# motor-shield.net
KiCad netlist of a schematic drawn in EAGLE
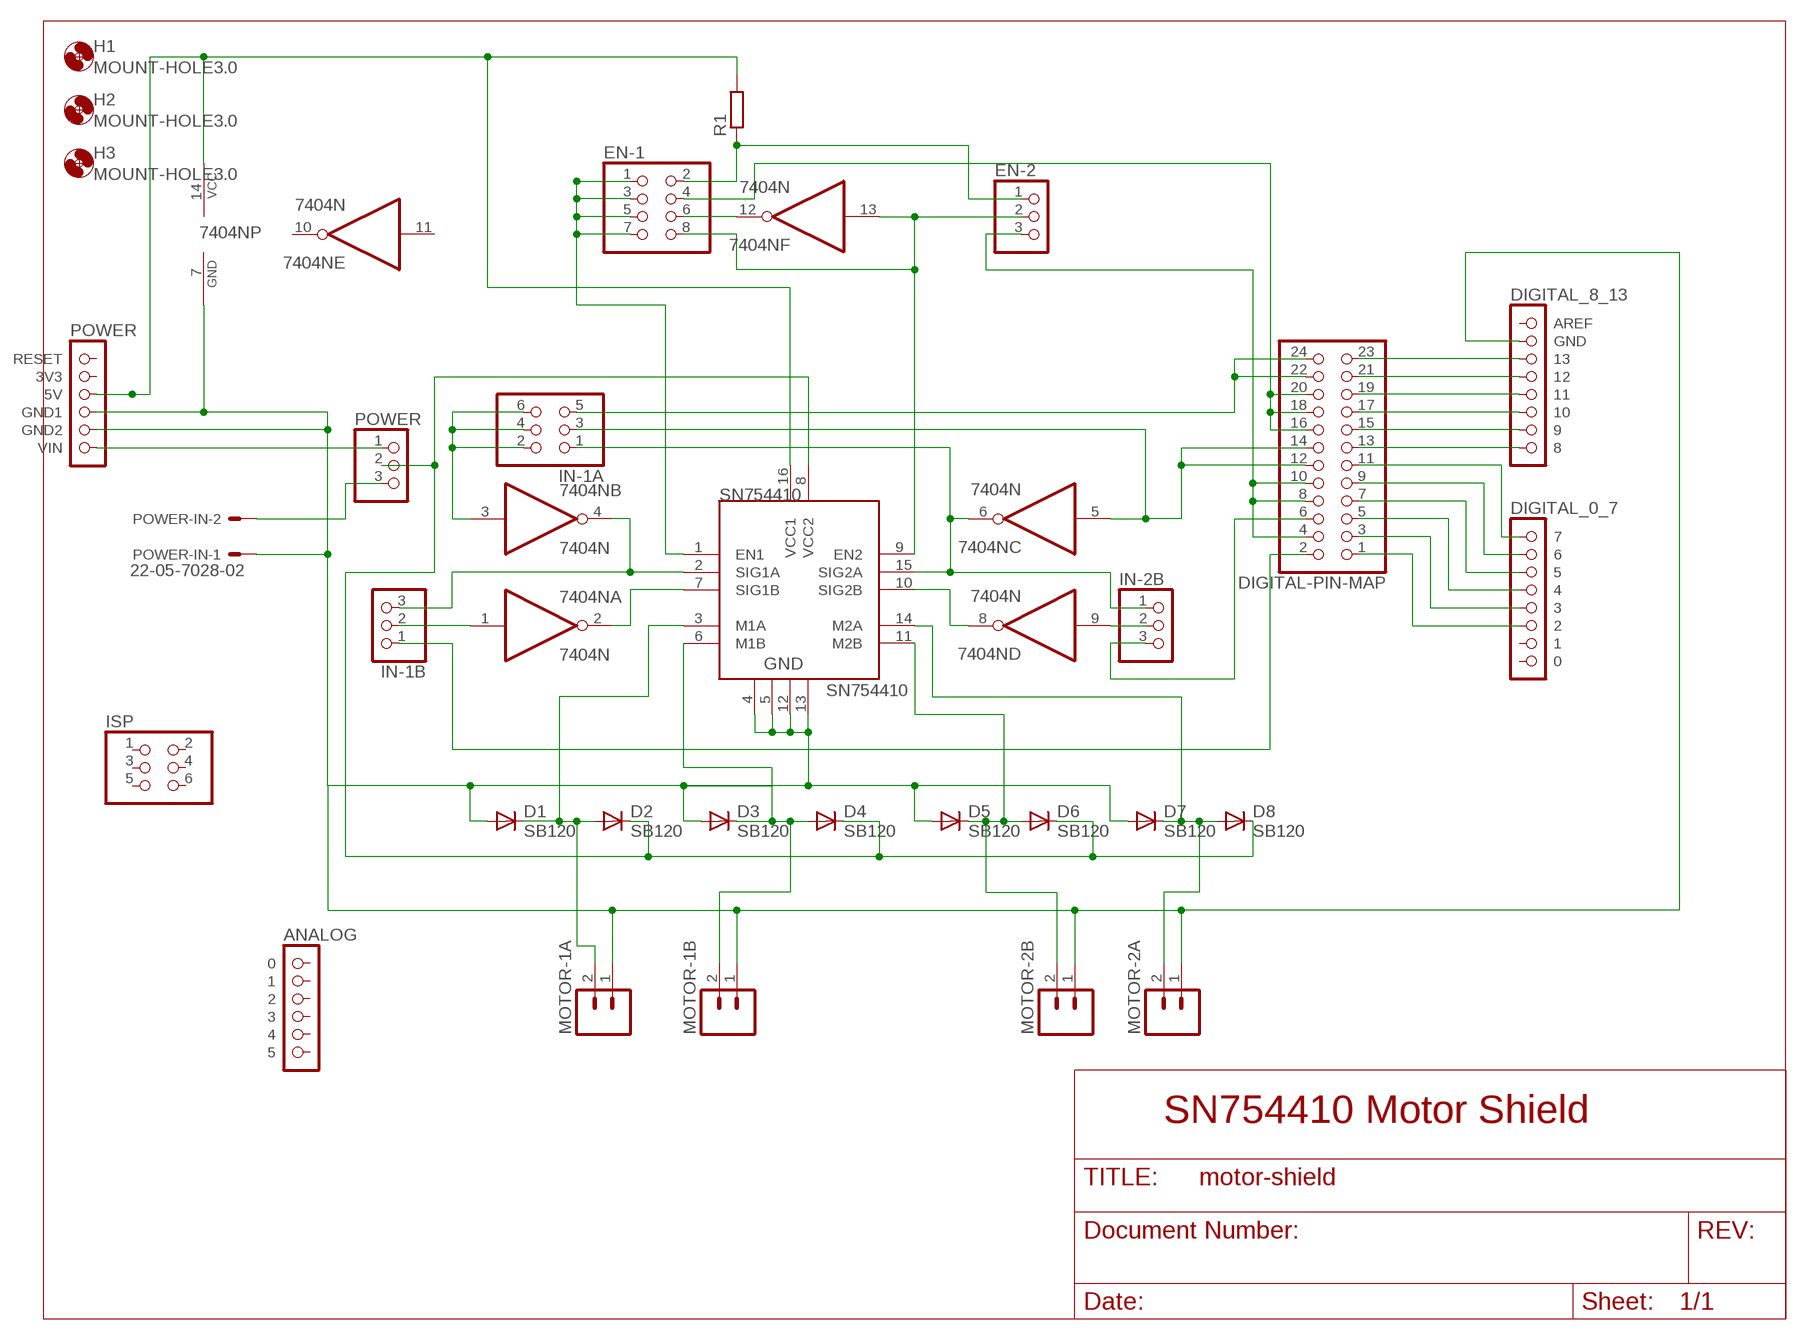
[diagram p0: schematic, sheet 1]

(export (version "E")
  (design (tool "Eeschema 10.0.6"))
  (components
    (comp (ref "7404N")
      (value "7404N")
      (footprint "eagle-import:DIL14")
      (libsource (lib "eagle-import") (part "7404N"))
    )
    (comp (ref "D1")
      (value "SB120")
      (footprint "eagle-import:DO41-10")
      (libsource (lib "eagle-import") (part "SB120"))
    )
    (comp (ref "D2")
      (value "SB120")
      (footprint "eagle-import:DO41-10")
      (libsource (lib "eagle-import") (part "SB120"))
    )
    (comp (ref "D3")
      (value "SB120")
      (footprint "eagle-import:DO41-10")
      (libsource (lib "eagle-import") (part "SB120"))
    )
    (comp (ref "D4")
      (value "SB120")
      (footprint "eagle-import:DO41-10")
      (libsource (lib "eagle-import") (part "SB120"))
    )
    (comp (ref "D5")
      (value "SB120")
      (footprint "eagle-import:DO41-10")
      (libsource (lib "eagle-import") (part "SB120"))
    )
    (comp (ref "D6")
      (value "SB120")
      (footprint "eagle-import:DO41-10")
      (libsource (lib "eagle-import") (part "SB120"))
    )
    (comp (ref "D7")
      (value "SB120")
      (footprint "eagle-import:DO41-10")
      (libsource (lib "eagle-import") (part "SB120"))
    )
    (comp (ref "D8")
      (value "SB120")
      (footprint "eagle-import:DO41-10")
      (libsource (lib "eagle-import") (part "SB120"))
    )
    (comp (ref "DIGITAL-PIN-MAP")
      (value "PINHD-2X12")
      (footprint "eagle-import:2X12")
      (libsource (lib "eagle-import") (part "PINHD-2X12"))
    )
    (comp (ref "EN-1")
      (value "PINHD-2X4")
      (footprint "eagle-import:2X04")
      (libsource (lib "eagle-import") (part "PINHD-2X4"))
    )
    (comp (ref "EN-2")
      (value "PINHD-1X3")
      (footprint "eagle-import:1X03")
      (libsource (lib "eagle-import") (part "PINHD-1X3"))
    )
    (comp (ref "H1")
      (value "MOUNT-HOLE3.0")
      (footprint "eagle-import:3,0")
      (libsource (lib "eagle-import") (part "MOUNT-HOLE3.0"))
    )
    (comp (ref "H2")
      (value "MOUNT-HOLE3.0")
      (footprint "eagle-import:3,0")
      (libsource (lib "eagle-import") (part "MOUNT-HOLE3.0"))
    )
    (comp (ref "H3")
      (value "MOUNT-HOLE3.0")
      (footprint "eagle-import:3,0")
      (libsource (lib "eagle-import") (part "MOUNT-HOLE3.0"))
    )
    (comp (ref "IN-1A")
      (value "PINHD-2X3")
      (footprint "eagle-import:2X03")
      (libsource (lib "eagle-import") (part "PINHD-2X3"))
    )
    (comp (ref "IN-1B")
      (value "PINHD-1X3")
      (footprint "eagle-import:1X03")
      (libsource (lib "eagle-import") (part "PINHD-1X3"))
    )
    (comp (ref "IN-2B")
      (value "PINHD-1X3")
      (footprint "eagle-import:1X03")
      (libsource (lib "eagle-import") (part "PINHD-1X3"))
    )
    (comp (ref "ISP")
      (value "PINHD-2X3")
      (footprint "eagle-import:2X03")
      (libsource (lib "eagle-import") (part "PINHD-2X3"))
    )
    (comp (ref "MOTOR-1A")
      (value "M023.5MM-NO_SILK")
      (footprint "eagle-import:SCREWTERMINAL-3.5MM-2-NS")
      (libsource (lib "eagle-import") (part "M023.5MM-NO_SILK"))
    )
    (comp (ref "MOTOR-1B")
      (value "M023.5MM-NO_SILK")
      (footprint "eagle-import:SCREWTERMINAL-3.5MM-2-NS")
      (libsource (lib "eagle-import") (part "M023.5MM-NO_SILK"))
    )
    (comp (ref "MOTOR-2A")
      (value "M023.5MM-NO_SILK")
      (footprint "eagle-import:SCREWTERMINAL-3.5MM-2-NS")
      (libsource (lib "eagle-import") (part "M023.5MM-NO_SILK"))
    )
    (comp (ref "MOTOR-2B")
      (value "M023.5MM-NO_SILK")
      (footprint "eagle-import:SCREWTERMINAL-3.5MM-2-NS")
      (libsource (lib "eagle-import") (part "M023.5MM-NO_SILK"))
    )
    (comp (ref "POWER")
      (value "PINHD-1X3")
      (footprint "eagle-import:1X03")
      (libsource (lib "eagle-import") (part "PINHD-1X3"))
    )
    (comp (ref "POWER-IN")
      (value "22-05-7028-02")
      (footprint "eagle-import:7395-02")
      (libsource (lib "eagle-import") (part "22-?-0205-7028"))
    )
    (comp (ref "R1")
      (value "R-EU_0207/10")
      (footprint "eagle-import:0207_10")
      (libsource (lib "eagle-import") (part "R-EU_0207/10"))
    )
    (comp (ref "SN754410")
      (value "SN754410")
      (footprint "eagle-import:DIP16")
      (libsource (lib "eagle-import") (part "SN754410"))
    )
    (comp (ref "U$1")
      (value "POWER")
      (footprint "eagle-import:1X06")
      (libsource (lib "eagle-import") (part "POWER"))
    )
    (comp (ref "U$2")
      (value "ANALOG")
      (footprint "eagle-import:1X06")
      (libsource (lib "eagle-import") (part "ANALOG"))
    )
    (comp (ref "U$3")
      (value "DIGITAL_0_7")
      (footprint "eagle-import:1X08")
      (libsource (lib "eagle-import") (part "DIGITAL_0_7"))
    )
    (comp (ref "U$4")
      (value "DIGITAL_8_13")
      (footprint "eagle-import:1X08")
      (libsource (lib "eagle-import") (part "DIGITAL_8_13"))
    )
  )
  (nets
    (net (code "1") (name "Net-(7404NA-I)") (class "Default")
      (node (ref "7404N") (pin "1") (pinfunction "I_1") (pintype "input"))
      (node (ref "IN-1B") (pin "2") (pinfunction "2_2") (pintype "passive"))
    )
    (net (code "2") (name "Net-(7404NA-O)") (class "Default")
      (node (ref "7404N") (pin "2") (pinfunction "O_2") (pintype "output"))
      (node (ref "SN754410") (pin "7") (pinfunction "SIG1B_7") (pintype "bidirectional"))
    )
    (net (code "3") (name "Net-(7404NB-I)") (class "Default")
      (node (ref "7404N") (pin "3") (pinfunction "I_3") (pintype "input"))
      (node (ref "IN-1A") (pin "2") (pinfunction "2_2") (pintype "passive"))
      (node (ref "IN-1A") (pin "4") (pinfunction "4_4") (pintype "passive"))
      (node (ref "IN-1A") (pin "6") (pinfunction "6_6") (pintype "passive"))
    )
    (net (code "4") (name "Net-(7404NB-O)") (class "Default")
      (node (ref "7404N") (pin "4") (pinfunction "O_4") (pintype "output"))
      (node (ref "IN-1B") (pin "3") (pinfunction "3_3") (pintype "passive"))
      (node (ref "SN754410") (pin "2") (pinfunction "SIG1A_2") (pintype "bidirectional"))
    )
    (net (code "5") (name "Net-(7404NC-I)") (class "Default")
      (node (ref "7404N") (pin "5") (pinfunction "I_5") (pintype "input"))
      (node (ref "DIGITAL-PIN-MAP") (pin "12") (pinfunction "12_12") (pintype "passive"))
      (node (ref "DIGITAL-PIN-MAP") (pin "14") (pinfunction "14_14") (pintype "passive"))
      (node (ref "IN-1A") (pin "3") (pinfunction "3_3") (pintype "passive"))
    )
    (net (code "6") (name "Net-(7404NC-O)") (class "Default")
      (node (ref "7404N") (pin "6") (pinfunction "O_6") (pintype "output"))
      (node (ref "IN-1A") (pin "1") (pinfunction "1_1") (pintype "passive"))
      (node (ref "IN-2B") (pin "1") (pinfunction "1_1") (pintype "passive"))
      (node (ref "SN754410") (pin "15") (pinfunction "SIG2A_15") (pintype "bidirectional"))
    )
    (net (code "7") (name "Net-(7404ND-I)") (class "Default")
      (node (ref "7404N") (pin "9") (pinfunction "I_9") (pintype "input"))
      (node (ref "IN-2B") (pin "2") (pinfunction "2_2") (pintype "passive"))
    )
    (net (code "8") (name "Net-(7404ND-O)") (class "Default")
      (node (ref "7404N") (pin "8") (pinfunction "O_8") (pintype "output"))
      (node (ref "SN754410") (pin "10") (pinfunction "SIG2B_10") (pintype "bidirectional"))
    )
    (net (code "9") (name "Net-(7404NF-I)") (class "Default")
      (node (ref "7404N") (pin "13") (pinfunction "I_13") (pintype "input"))
      (node (ref "EN-1") (pin "8") (pinfunction "8_8") (pintype "passive"))
      (node (ref "EN-2") (pin "2") (pinfunction "2_2") (pintype "passive"))
      (node (ref "SN754410") (pin "9") (pinfunction "EN2_9") (pintype "bidirectional"))
    )
    (net (code "10") (name "Net-(7404NF-O)") (class "Default")
      (node (ref "7404N") (pin "12") (pinfunction "O_12") (pintype "output"))
      (node (ref "EN-1") (pin "6") (pinfunction "6_6") (pintype "passive"))
    )
    (net (code "11") (name "Net-(7404NG-GND)") (class "Default")
      (node (ref "7404N") (pin "7") (pinfunction "GND_7") (pintype "power_in"))
      (node (ref "D1") (pin "A") (pinfunction "A_A") (pintype "passive"))
      (node (ref "D3") (pin "A") (pinfunction "A_A") (pintype "passive"))
      (node (ref "D5") (pin "A") (pinfunction "A_A") (pintype "passive"))
      (node (ref "D7") (pin "A") (pinfunction "A_A") (pintype "passive"))
      (node (ref "MOTOR-1A") (pin "1") (pinfunction "1_1") (pintype "passive"))
      (node (ref "MOTOR-1B") (pin "1") (pinfunction "1_1") (pintype "passive"))
      (node (ref "MOTOR-2A") (pin "1") (pinfunction "1_1") (pintype "passive"))
      (node (ref "MOTOR-2B") (pin "1") (pinfunction "1_1") (pintype "passive"))
      (node (ref "POWER-IN") (pin "1") (pinfunction "S_1") (pintype "passive"))
      (node (ref "SN754410") (pin "12") (pinfunction "P12_12") (pintype "power_in"))
      (node (ref "SN754410") (pin "13") (pinfunction "P13_13") (pintype "power_in"))
      (node (ref "SN754410") (pin "4") (pinfunction "P4_4") (pintype "power_in"))
      (node (ref "SN754410") (pin "5") (pinfunction "P5_5") (pintype "power_in"))
      (node (ref "U$1") (pin "4") (pinfunction "GND1_4") (pintype "passive"))
      (node (ref "U$1") (pin "5") (pinfunction "GND2_5") (pintype "passive"))
      (node (ref "U$4") (pin "2") (pinfunction "GND_2") (pintype "passive"))
    )
    (net (code "12") (name "Net-(7404NG-VCC)") (class "Default")
      (node (ref "7404N") (pin "14") (pinfunction "VCC_14") (pintype "power_in"))
      (node (ref "R1") (pin "2") (pinfunction "2_2") (pintype "passive"))
      (node (ref "SN754410") (pin "16") (pinfunction "VCC1_16") (pintype "power_in"))
      (node (ref "U$1") (pin "3") (pinfunction "5V_3") (pintype "passive"))
    )
    (net (code "13") (name "Net-(DIGITAL-PIN-MAP-Pad2)") (class "Default")
      (node (ref "DIGITAL-PIN-MAP") (pin "2") (pinfunction "2_2") (pintype "passive"))
      (node (ref "IN-1B") (pin "1") (pinfunction "1_1") (pintype "passive"))
    )
    (net (code "14") (name "Net-(DIGITAL-PIN-MAP-Pad5)") (class "Default")
      (node (ref "DIGITAL-PIN-MAP") (pin "5") (pinfunction "5_5") (pintype "passive"))
      (node (ref "U$3") (pin "4") (pinfunction "4_4") (pintype "passive"))
    )
    (net (code "15") (name "Net-(DIGITAL-PIN-MAP-Pad6)") (class "Default")
      (node (ref "DIGITAL-PIN-MAP") (pin "6") (pinfunction "6_6") (pintype "passive"))
      (node (ref "IN-2B") (pin "3") (pinfunction "3_3") (pintype "passive"))
    )
    (net (code "16") (name "Net-(DIGITAL-PIN-MAP-Pad10)") (class "Default")
      (node (ref "DIGITAL-PIN-MAP") (pin "10") (pinfunction "10_10") (pintype "passive"))
      (node (ref "DIGITAL-PIN-MAP") (pin "4") (pinfunction "4_4") (pintype "passive"))
      (node (ref "DIGITAL-PIN-MAP") (pin "8") (pinfunction "8_8") (pintype "passive"))
      (node (ref "EN-2") (pin "3") (pinfunction "3_3") (pintype "passive"))
    )
    (net (code "17") (name "Net-(DIGITAL-PIN-MAP-Pad13)") (class "Default")
      (node (ref "DIGITAL-PIN-MAP") (pin "13") (pinfunction "13_13") (pintype "passive"))
      (node (ref "U$4") (pin "8") (pinfunction "8_8") (pintype "passive"))
    )
    (net (code "18") (name "Net-(DIGITAL-PIN-MAP-Pad16)") (class "Default")
      (node (ref "DIGITAL-PIN-MAP") (pin "16") (pinfunction "16_16") (pintype "passive"))
      (node (ref "DIGITAL-PIN-MAP") (pin "18") (pinfunction "18_18") (pintype "passive"))
      (node (ref "DIGITAL-PIN-MAP") (pin "20") (pinfunction "20_20") (pintype "passive"))
      (node (ref "EN-1") (pin "4") (pinfunction "4_4") (pintype "passive"))
    )
    (net (code "19") (name "Net-(DIGITAL-PIN-MAP-Pad22)") (class "Default")
      (node (ref "DIGITAL-PIN-MAP") (pin "22") (pinfunction "22_22") (pintype "passive"))
      (node (ref "DIGITAL-PIN-MAP") (pin "24") (pinfunction "24_24") (pintype "passive"))
      (node (ref "IN-1A") (pin "5") (pinfunction "5_5") (pintype "passive"))
    )
    (net (code "20") (name "Net-(EN-1-Pad2)") (class "Default")
      (node (ref "EN-1") (pin "2") (pinfunction "2_2") (pintype "passive"))
      (node (ref "EN-2") (pin "1") (pinfunction "1_1") (pintype "passive"))
      (node (ref "R1") (pin "1") (pinfunction "1_1") (pintype "passive"))
    )
    (net (code "21") (name "Net-(POWER-INB-S)") (class "Default")
      (node (ref "POWER") (pin "3") (pinfunction "3_3") (pintype "passive"))
      (node (ref "POWER-IN") (pin "2") (pinfunction "S_2") (pintype "passive"))
    )
    (net (code "22") (name "Net-(SN754410-EN1)") (class "Default")
      (node (ref "EN-1") (pin "1") (pinfunction "1_1") (pintype "passive"))
      (node (ref "EN-1") (pin "3") (pinfunction "3_3") (pintype "passive"))
      (node (ref "EN-1") (pin "5") (pinfunction "5_5") (pintype "passive"))
      (node (ref "EN-1") (pin "7") (pinfunction "7_7") (pintype "passive"))
      (node (ref "SN754410") (pin "1") (pinfunction "EN1_1") (pintype "bidirectional"))
    )
    (net (code "23") (name "Net-(SN754410-M1A)") (class "Default")
      (node (ref "D1") (pin "C") (pinfunction "C_C") (pintype "passive"))
      (node (ref "D2") (pin "A") (pinfunction "A_A") (pintype "passive"))
      (node (ref "MOTOR-1A") (pin "2") (pinfunction "2_2") (pintype "passive"))
      (node (ref "SN754410") (pin "3") (pinfunction "M1A_3") (pintype "bidirectional"))
    )
    (net (code "24") (name "Net-(SN754410-M1B)") (class "Default")
      (node (ref "D3") (pin "C") (pinfunction "C_C") (pintype "passive"))
      (node (ref "D4") (pin "A") (pinfunction "A_A") (pintype "passive"))
      (node (ref "MOTOR-1B") (pin "2") (pinfunction "2_2") (pintype "passive"))
      (node (ref "SN754410") (pin "6") (pinfunction "M1B_6") (pintype "bidirectional"))
    )
    (net (code "25") (name "Net-(SN754410-M2A)") (class "Default")
      (node (ref "D7") (pin "C") (pinfunction "C_C") (pintype "passive"))
      (node (ref "D8") (pin "A") (pinfunction "A_A") (pintype "passive"))
      (node (ref "MOTOR-2A") (pin "2") (pinfunction "2_2") (pintype "passive"))
      (node (ref "SN754410") (pin "14") (pinfunction "M2A_14") (pintype "bidirectional"))
    )
    (net (code "26") (name "Net-(SN754410-M2B)") (class "Default")
      (node (ref "D5") (pin "C") (pinfunction "C_C") (pintype "passive"))
      (node (ref "D6") (pin "A") (pinfunction "A_A") (pintype "passive"))
      (node (ref "MOTOR-2B") (pin "2") (pinfunction "2_2") (pintype "passive"))
      (node (ref "SN754410") (pin "11") (pinfunction "M2B_11") (pintype "bidirectional"))
    )
    (net (code "27") (name "Net-(SN754410-VCC2)") (class "Default")
      (node (ref "D2") (pin "C") (pinfunction "C_C") (pintype "passive"))
      (node (ref "D4") (pin "C") (pinfunction "C_C") (pintype "passive"))
      (node (ref "D6") (pin "C") (pinfunction "C_C") (pintype "passive"))
      (node (ref "D8") (pin "C") (pinfunction "C_C") (pintype "passive"))
      (node (ref "POWER") (pin "2") (pinfunction "2_2") (pintype "passive"))
      (node (ref "SN754410") (pin "8") (pinfunction "VCC2_8") (pintype "power_in"))
    )
    (net (code "28") (name "Net-(U$1-VIN)") (class "Default")
      (node (ref "POWER") (pin "1") (pinfunction "1_1") (pintype "passive"))
      (node (ref "U$1") (pin "6") (pinfunction "VIN_6") (pintype "passive"))
    )
    (net (code "29") (name "Net-(U$3-2)") (class "Default")
      (node (ref "DIGITAL-PIN-MAP") (pin "1") (pinfunction "1_1") (pintype "passive"))
      (node (ref "U$3") (pin "6") (pinfunction "2_6") (pintype "passive"))
    )
    (net (code "30") (name "Net-(U$3-3)") (class "Default")
      (node (ref "DIGITAL-PIN-MAP") (pin "3") (pinfunction "3_3") (pintype "passive"))
      (node (ref "U$3") (pin "5") (pinfunction "3_5") (pintype "passive"))
    )
    (net (code "31") (name "Net-(U$3-5)") (class "Default")
      (node (ref "DIGITAL-PIN-MAP") (pin "7") (pinfunction "7_7") (pintype "passive"))
      (node (ref "U$3") (pin "3") (pinfunction "5_3") (pintype "passive"))
    )
    (net (code "32") (name "Net-(U$3-6)") (class "Default")
      (node (ref "DIGITAL-PIN-MAP") (pin "9") (pinfunction "9_9") (pintype "passive"))
      (node (ref "U$3") (pin "2") (pinfunction "6_2") (pintype "passive"))
    )
    (net (code "33") (name "Net-(U$3-7)") (class "Default")
      (node (ref "DIGITAL-PIN-MAP") (pin "11") (pinfunction "11_11") (pintype "passive"))
      (node (ref "U$3") (pin "1") (pinfunction "7_1") (pintype "passive"))
    )
    (net (code "34") (name "Net-(U$4-9)") (class "Default")
      (node (ref "DIGITAL-PIN-MAP") (pin "15") (pinfunction "15_15") (pintype "passive"))
      (node (ref "U$4") (pin "7") (pinfunction "9_7") (pintype "passive"))
    )
    (net (code "35") (name "Net-(U$4-10)") (class "Default")
      (node (ref "DIGITAL-PIN-MAP") (pin "17") (pinfunction "17_17") (pintype "passive"))
      (node (ref "U$4") (pin "6") (pinfunction "10_6") (pintype "passive"))
    )
    (net (code "36") (name "Net-(U$4-11)") (class "Default")
      (node (ref "DIGITAL-PIN-MAP") (pin "19") (pinfunction "19_19") (pintype "passive"))
      (node (ref "U$4") (pin "5") (pinfunction "11_5") (pintype "passive"))
    )
    (net (code "37") (name "Net-(U$4-12)") (class "Default")
      (node (ref "DIGITAL-PIN-MAP") (pin "21") (pinfunction "21_21") (pintype "passive"))
      (node (ref "U$4") (pin "4") (pinfunction "12_4") (pintype "passive"))
    )
    (net (code "38") (name "Net-(U$4-13)") (class "Default")
      (node (ref "DIGITAL-PIN-MAP") (pin "23") (pinfunction "23_23") (pintype "passive"))
      (node (ref "U$4") (pin "3") (pinfunction "13_3") (pintype "passive"))
    )
    (net (code "39") (name "unconnected-(7404NE-I-Pad11)") (class "Default")
      (node (ref "7404N") (pin "11") (pinfunction "I_11") (pintype "input"))
    )
    (net (code "40") (name "unconnected-(7404NE-O-Pad10)") (class "Default")
      (node (ref "7404N") (pin "10") (pinfunction "O_10") (pintype "output"))
    )
    (net (code "41") (name "unconnected-(ISP-Pad1)") (class "Default")
      (node (ref "ISP") (pin "1") (pinfunction "1_1") (pintype "passive"))
    )
    (net (code "42") (name "unconnected-(ISP-Pad2)") (class "Default")
      (node (ref "ISP") (pin "2") (pinfunction "2_2") (pintype "passive"))
    )
    (net (code "43") (name "unconnected-(ISP-Pad3)") (class "Default")
      (node (ref "ISP") (pin "3") (pinfunction "3_3") (pintype "passive"))
    )
    (net (code "44") (name "unconnected-(ISP-Pad4)") (class "Default")
      (node (ref "ISP") (pin "4") (pinfunction "4_4") (pintype "passive"))
    )
    (net (code "45") (name "unconnected-(ISP-Pad5)") (class "Default")
      (node (ref "ISP") (pin "5") (pinfunction "5_5") (pintype "passive"))
    )
    (net (code "46") (name "unconnected-(ISP-Pad6)") (class "Default")
      (node (ref "ISP") (pin "6") (pinfunction "6_6") (pintype "passive"))
    )
    (net (code "47") (name "unconnected-(U$1-3V3-Pad2)") (class "Default")
      (node (ref "U$1") (pin "2") (pinfunction "3V3_2") (pintype "passive"))
    )
    (net (code "48") (name "unconnected-(U$1-RESET-Pad1)") (class "Default")
      (node (ref "U$1") (pin "1") (pinfunction "RESET_1") (pintype "passive"))
    )
    (net (code "49") (name "unconnected-(U$2-0-Pad1)") (class "Default")
      (node (ref "U$2") (pin "1") (pinfunction "0_1") (pintype "passive"))
    )
    (net (code "50") (name "unconnected-(U$2-1-Pad2)") (class "Default")
      (node (ref "U$2") (pin "2") (pinfunction "1_2") (pintype "passive"))
    )
    (net (code "51") (name "unconnected-(U$2-2-Pad3)") (class "Default")
      (node (ref "U$2") (pin "3") (pinfunction "2_3") (pintype "passive"))
    )
    (net (code "52") (name "unconnected-(U$2-3-Pad4)") (class "Default")
      (node (ref "U$2") (pin "4") (pinfunction "3_4") (pintype "passive"))
    )
    (net (code "53") (name "unconnected-(U$2-4-Pad5)") (class "Default")
      (node (ref "U$2") (pin "5") (pinfunction "4_5") (pintype "passive"))
    )
    (net (code "54") (name "unconnected-(U$2-5-Pad6)") (class "Default")
      (node (ref "U$2") (pin "6") (pinfunction "5_6") (pintype "passive"))
    )
    (net (code "55") (name "unconnected-(U$3-0-Pad8)") (class "Default")
      (node (ref "U$3") (pin "8") (pinfunction "0_8") (pintype "passive"))
    )
    (net (code "56") (name "unconnected-(U$3-1-Pad7)") (class "Default")
      (node (ref "U$3") (pin "7") (pinfunction "1_7") (pintype "passive"))
    )
    (net (code "57") (name "unconnected-(U$4-AREF-Pad1)") (class "Default")
      (node (ref "U$4") (pin "1") (pinfunction "AREF_1") (pintype "passive"))
    )
  )
)
